# dBFS_Conditioning.net
KiCad netlist of a schematic drawn in Altium Designer
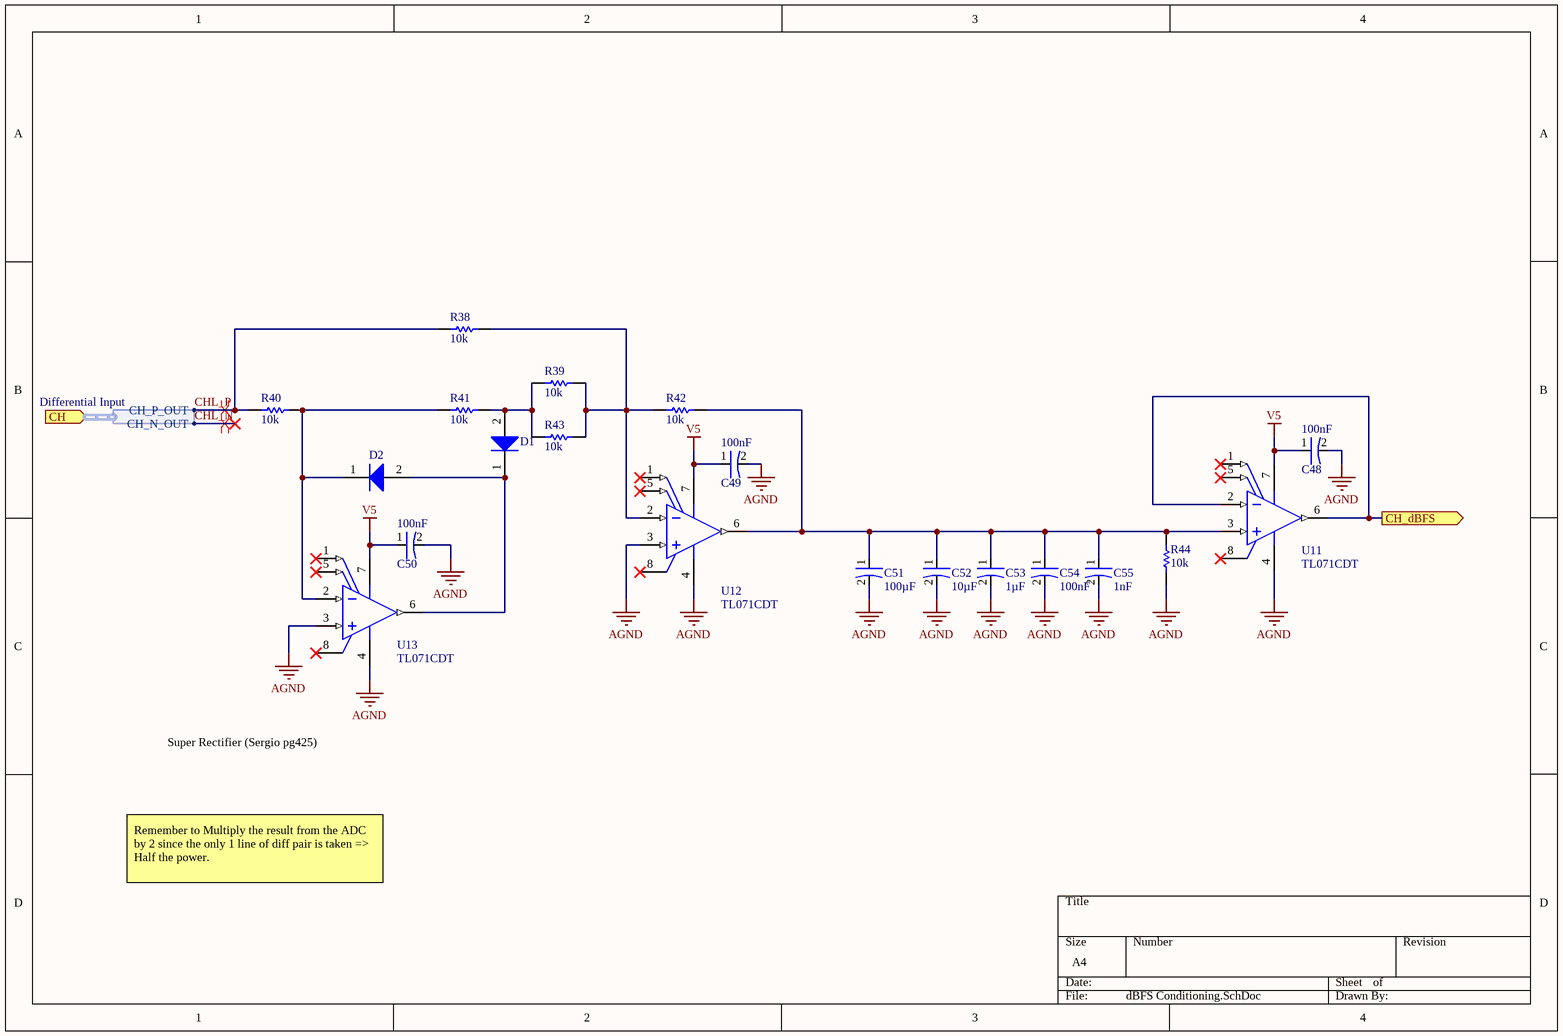
[diagram p0: dBFS Conditioning.SchDoc]

(export (version "E")
  (design (tool "Eeschema 10.0.6"))
  (components
    (comp (ref "C48")
      (value "100nF")
      (footprint "0805-M")
      (description "CAP-0.1uF-CER-0805-50V- X7R-5%")
      (fields
        (field (name "MANUFACTURER") "Generic")
        (field (name "Comment") "CAP 0.1uF CER 0805 50V  X7R 5%")
      )
      (libsource (lib "") (part "Symbol_1"))
    )
    (comp (ref "C49")
      (value "100nF")
      (footprint "0805-M")
      (description "CAP-0.1uF-CER-0805-50V- X7R-5%")
      (fields
        (field (name "MANUFACTURER") "Generic")
        (field (name "Comment") "CAP 0.1uF CER 0805 50V  X7R 5%")
      )
      (libsource (lib "") (part "Symbol_1"))
    )
    (comp (ref "C50")
      (value "100nF")
      (footprint "0805-M")
      (description "CAP-0.1uF-CER-0805-50V- X7R-5%")
      (fields
        (field (name "MANUFACTURER") "Generic")
        (field (name "Comment") "CAP 0.1uF CER 0805 50V  X7R 5%")
      )
      (libsource (lib "") (part "Symbol_1"))
    )
    (comp (ref "C51")
      (value "100µF")
      (footprint "1210-M")
      (description "CAP-100uF-CER-1210-16V-X5R-20%")
      (fields
        (field (name "MANUFACTURER") "Generic")
        (field (name "Comment") "CAP 100uF CER 1210 16V X5R 20%")
      )
      (libsource (lib "") (part "Symbol_1"))
    )
    (comp (ref "C52")
      (value "10µF")
      (footprint "0805-M")
      (description "CAP-10uF-CER-0805-25V-X5R-10%")
      (fields
        (field (name "MANUFACTURER") "Generic")
        (field (name "Comment") "CAP 10uF CER 0805 25V X5R 10%")
      )
      (libsource (lib "") (part "Symbol_1"))
    )
    (comp (ref "C53")
      (value "1µF")
      (footprint "0805-M")
      (description "CAP 1uF CER 0805 25V C0G 10%")
      (fields (field (name "MANUFACTURER") "Generic"))
      (libsource (lib "") (part "Symbol_1"))
    )
    (comp (ref "C54")
      (value "100nF")
      (footprint "0805-M")
      (description "CAP-0.1uF-CER-0805-50V- X7R-5%")
      (fields
        (field (name "MANUFACTURER") "Generic")
        (field (name "Comment") "CAP 0.1uF CER 0805 50V  X7R 5%")
      )
      (libsource (lib "") (part "Symbol_1"))
    )
    (comp (ref "C55")
      (value "1nF")
      (footprint "0805-M")
      (description "CAP 1nF CER 0805 25V X7R 5%")
      (fields (field (name "MANUFACTURER") "Generic"))
      (libsource (lib "") (part "Symbol_1"))
    )
    (comp (ref "D1")
      (value "1N4148W-7-F")
      (footprint "SODFL370X135-2M")
      (description "DIODE-SMT-1.25V-100V-0.15A-1N4148")
      (fields (field (name "MANUFACTURER") "Vishay"))
      (libsource (lib "") (part "Symbol_2"))
    )
    (comp (ref "D2")
      (value "1N4148W-7-F")
      (footprint "SODFL370X135-2M")
      (description "DIODE-SMT-1.25V-100V-0.15A-1N4148")
      (fields (field (name "MANUFACTURER") "Vishay"))
      (libsource (lib "") (part "Symbol_2"))
    )
    (comp (ref "R38")
      (value "10k")
      (footprint "0805-M")
      (description "RES-10k-0805-125mW-1%")
      (fields (field (name "MANUFACTURER") "Generic") (field (name "Comment") "RES 10k 0805 125mW 1%"))
      (libsource (lib "University of Malta - MEMENTO") (part "Symbol"))
    )
    (comp (ref "R39")
      (value "10k")
      (footprint "0805-M")
      (description "RES-10k-0805-125mW-1%")
      (fields (field (name "MANUFACTURER") "Generic") (field (name "Comment") "RES 10k 0805 125mW 1%"))
      (libsource (lib "University of Malta - MEMENTO") (part "Symbol"))
    )
    (comp (ref "R40")
      (value "10k")
      (footprint "0805-M")
      (description "RES-10k-0805-125mW-1%")
      (fields (field (name "MANUFACTURER") "Generic") (field (name "Comment") "RES 10k 0805 125mW 1%"))
      (libsource (lib "University of Malta - MEMENTO") (part "Symbol"))
    )
    (comp (ref "R41")
      (value "10k")
      (footprint "0805-M")
      (description "RES-10k-0805-125mW-1%")
      (fields (field (name "MANUFACTURER") "Generic") (field (name "Comment") "RES 10k 0805 125mW 1%"))
      (libsource (lib "University of Malta - MEMENTO") (part "Symbol"))
    )
    (comp (ref "R42")
      (value "10k")
      (footprint "0805-M")
      (description "RES-10k-0805-125mW-1%")
      (fields (field (name "MANUFACTURER") "Generic") (field (name "Comment") "RES 10k 0805 125mW 1%"))
      (libsource (lib "University of Malta - MEMENTO") (part "Symbol"))
    )
    (comp (ref "R43")
      (value "10k")
      (footprint "0805-M")
      (description "RES-10k-0805-125mW-1%")
      (fields (field (name "MANUFACTURER") "Generic") (field (name "Comment") "RES 10k 0805 125mW 1%"))
      (libsource (lib "University of Malta - MEMENTO") (part "Symbol"))
    )
    (comp (ref "R44")
      (value "10k")
      (footprint "0805-M")
      (description "RES-10k-0805-125mW-1%")
      (fields (field (name "MANUFACTURER") "Generic") (field (name "Comment") "RES 10k 0805 125mW 1%"))
      (libsource (lib "University of Malta - MEMENTO") (part "Symbol"))
    )
    (comp (ref "U11")
      (value "TL071CDT")
      (footprint "SOP127P600X175-8N")
      (description "IC OPAMP JFET 4MHZ 8SO")
      (fields (field (name "MANUFACTURER") "STMicroelectronics"))
      (libsource (lib "University of Malta - MEMENTO") (part "TL071CDT"))
    )
    (comp (ref "U12")
      (value "TL071CDT")
      (footprint "SOP127P600X175-8N")
      (description "IC OPAMP JFET 4MHZ 8SO")
      (fields (field (name "MANUFACTURER") "STMicroelectronics"))
      (libsource (lib "University of Malta - MEMENTO") (part "TL071CDT"))
    )
    (comp (ref "U13")
      (value "TL071CDT")
      (footprint "SOP127P600X175-8N")
      (description "IC OPAMP JFET 4MHZ 8SO")
      (fields (field (name "MANUFACTURER") "STMicroelectronics"))
      (libsource (lib "University of Malta - MEMENTO") (part "TL071CDT"))
    )
  )
  (nets
    (net (code "4") (name "/CHL_P") (class "Default")
      (node (ref "R38") (pin "1") (pinfunction "1_1") (pintype "passive"))
      (node (ref "R40") (pin "1") (pinfunction "1_1") (pintype "passive"))
    )
    (net (code "5") (name "/CH_dBFS") (class "Default")
      (node (ref "U11") (pin "2") (pinfunction "Inverting_Input_2") (pintype "input"))
      (node (ref "U11") (pin "6") (pinfunction "OUT_6") (pintype "output"))
    )
    (net (code "7") (name "AGND") (class "Default")
      (node (ref "C48") (pin "2") (pinfunction "Cathode_2") (pintype "passive"))
      (node (ref "C49") (pin "2") (pinfunction "Cathode_2") (pintype "passive"))
      (node (ref "C50") (pin "2") (pinfunction "Cathode_2") (pintype "passive"))
      (node (ref "C51") (pin "2") (pinfunction "Cathode_2") (pintype "passive"))
      (node (ref "C52") (pin "2") (pinfunction "Cathode_2") (pintype "passive"))
      (node (ref "C53") (pin "2") (pinfunction "Cathode_2") (pintype "passive"))
      (node (ref "C54") (pin "2") (pinfunction "Cathode_2") (pintype "passive"))
      (node (ref "C55") (pin "2") (pinfunction "Cathode_2") (pintype "passive"))
      (node (ref "R44") (pin "1") (pinfunction "1_1") (pintype "passive"))
      (node (ref "U11") (pin "4") (pinfunction "V-_4") (pintype "power_in"))
      (node (ref "U12") (pin "3") (pinfunction "Non_Inverting_Input_3") (pintype "input"))
      (node (ref "U12") (pin "4") (pinfunction "V-_4") (pintype "power_in"))
      (node (ref "U13") (pin "3") (pinfunction "Non_Inverting_Input_3") (pintype "input"))
      (node (ref "U13") (pin "4") (pinfunction "V-_4") (pintype "power_in"))
    )
    (net (code "8") (name "Net-(C51-Anode)") (class "Default")
      (node (ref "C51") (pin "1") (pinfunction "Anode_1") (pintype "passive"))
      (node (ref "C52") (pin "1") (pinfunction "Anode_1") (pintype "passive"))
      (node (ref "C53") (pin "1") (pinfunction "Anode_1") (pintype "passive"))
      (node (ref "C54") (pin "1") (pinfunction "Anode_1") (pintype "passive"))
      (node (ref "C55") (pin "1") (pinfunction "Anode_1") (pintype "passive"))
      (node (ref "R42") (pin "2") (pinfunction "2_2") (pintype "passive"))
      (node (ref "R44") (pin "2") (pinfunction "2_2") (pintype "passive"))
      (node (ref "U11") (pin "3") (pinfunction "Non_Inverting_Input_3") (pintype "input"))
      (node (ref "U12") (pin "6") (pinfunction "OUT_6") (pintype "output"))
    )
    (net (code "9") (name "Net-(D1-Pad2)") (class "Default")
      (node (ref "D1") (pin "2") (pinfunction "2_2") (pintype "passive"))
      (node (ref "R39") (pin "1") (pinfunction "1_1") (pintype "passive"))
      (node (ref "R41") (pin "2") (pinfunction "2_2") (pintype "passive"))
      (node (ref "R43") (pin "1") (pinfunction "1_1") (pintype "passive"))
    )
    (net (code "10") (name "Net-(U12-Inverting_Input)") (class "Default")
      (node (ref "R38") (pin "2") (pinfunction "2_2") (pintype "passive"))
      (node (ref "R39") (pin "2") (pinfunction "2_2") (pintype "passive"))
      (node (ref "R42") (pin "1") (pinfunction "1_1") (pintype "passive"))
      (node (ref "R43") (pin "2") (pinfunction "2_2") (pintype "passive"))
      (node (ref "U12") (pin "2") (pinfunction "Inverting_Input_2") (pintype "input"))
    )
    (net (code "11") (name "Net-(U13-Inverting_Input)") (class "Default")
      (node (ref "D2") (pin "1") (pinfunction "1_1") (pintype "passive"))
      (node (ref "R40") (pin "2") (pinfunction "2_2") (pintype "passive"))
      (node (ref "R41") (pin "1") (pinfunction "1_1") (pintype "passive"))
      (node (ref "U13") (pin "2") (pinfunction "Inverting_Input_2") (pintype "input"))
    )
    (net (code "12") (name "Net-(U13-OUT)") (class "Default")
      (node (ref "D1") (pin "1") (pinfunction "1_1") (pintype "passive"))
      (node (ref "D2") (pin "2") (pinfunction "2_2") (pintype "passive"))
      (node (ref "U13") (pin "6") (pinfunction "OUT_6") (pintype "output"))
    )
    (net (code "13") (name "V5") (class "Default")
      (node (ref "C48") (pin "1") (pinfunction "Anode_1") (pintype "passive"))
      (node (ref "C49") (pin "1") (pinfunction "Anode_1") (pintype "passive"))
      (node (ref "C50") (pin "1") (pinfunction "Anode_1") (pintype "passive"))
      (node (ref "U11") (pin "7") (pinfunction "V+_7") (pintype "power_in"))
      (node (ref "U12") (pin "7") (pinfunction "V+_7") (pintype "power_in"))
      (node (ref "U13") (pin "7") (pinfunction "V+_7") (pintype "power_in"))
    )
    (net (code "14") (name "unconnected-(U11-NC-Pad8)") (class "Default")
      (node (ref "U11") (pin "8") (pinfunction "NC_8") (pintype "passive+no_connect"))
    )
    (net (code "15") (name "unconnected-(U11-Offset_Null_1-Pad1)") (class "Default")
      (node (ref "U11") (pin "1") (pinfunction "Offset_Null_1_1") (pintype "input+no_connect"))
    )
    (net (code "16") (name "unconnected-(U11-Offset_Null_2-Pad5)") (class "Default")
      (node (ref "U11") (pin "5") (pinfunction "Offset_Null_2_5") (pintype "input+no_connect"))
    )
    (net (code "17") (name "unconnected-(U12-NC-Pad8)") (class "Default")
      (node (ref "U12") (pin "8") (pinfunction "NC_8") (pintype "passive+no_connect"))
    )
    (net (code "18") (name "unconnected-(U12-Offset_Null_1-Pad1)") (class "Default")
      (node (ref "U12") (pin "1") (pinfunction "Offset_Null_1_1") (pintype "input+no_connect"))
    )
    (net (code "19") (name "unconnected-(U12-Offset_Null_2-Pad5)") (class "Default")
      (node (ref "U12") (pin "5") (pinfunction "Offset_Null_2_5") (pintype "input+no_connect"))
    )
    (net (code "20") (name "unconnected-(U13-NC-Pad8)") (class "Default")
      (node (ref "U13") (pin "8") (pinfunction "NC_8") (pintype "passive+no_connect"))
    )
    (net (code "21") (name "unconnected-(U13-Offset_Null_1-Pad1)") (class "Default")
      (node (ref "U13") (pin "1") (pinfunction "Offset_Null_1_1") (pintype "input+no_connect"))
    )
    (net (code "22") (name "unconnected-(U13-Offset_Null_2-Pad5)") (class "Default")
      (node (ref "U13") (pin "5") (pinfunction "Offset_Null_2_5") (pintype "input+no_connect"))
    )
  )
)
